# dwm1000v3.net
KiCad netlist of a schematic drawn in EAGLE
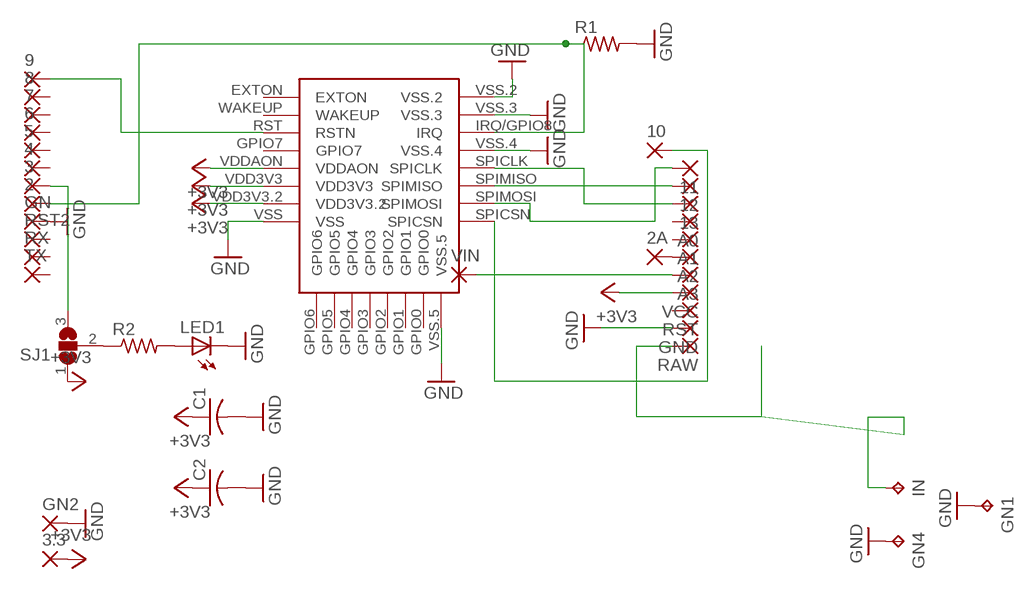
[diagram p0: schematic, sheet 1]

(export (version "E")
  (design (tool "Eeschema 10.0.6"))
  (components
    (comp (ref "2")
      (value "SMD2")
      (footprint "eagle-import:SMD1,27-2,54")
      (libsource (lib "eagle-import") (part "SMD2"))
    )
    (comp (ref "2A")
      (value "SMD2")
      (footprint "eagle-import:SMD1,27-2,54")
      (libsource (lib "eagle-import") (part "SMD2"))
    )
    (comp (ref "3")
      (value "SMD2")
      (footprint "eagle-import:SMD1,27-2,54")
      (libsource (lib "eagle-import") (part "SMD2"))
    )
    (comp (ref "3.3")
      (value "SMD2")
      (footprint "eagle-import:SMD1,27-2,54")
      (libsource (lib "eagle-import") (part "SMD2"))
    )
    (comp (ref "4")
      (value "SMD2")
      (footprint "eagle-import:SMD1,27-2,54")
      (libsource (lib "eagle-import") (part "SMD2"))
    )
    (comp (ref "5")
      (value "SMD2")
      (footprint "eagle-import:SMD1,27-2,54")
      (libsource (lib "eagle-import") (part "SMD2"))
    )
    (comp (ref "6")
      (value "SMD2")
      (footprint "eagle-import:SMD1,27-2,54")
      (libsource (lib "eagle-import") (part "SMD2"))
    )
    (comp (ref "7")
      (value "SMD2")
      (footprint "eagle-import:SMD1,27-2,54")
      (libsource (lib "eagle-import") (part "SMD2"))
    )
    (comp (ref "8")
      (value "SMD2")
      (footprint "eagle-import:SMD1,27-2,54")
      (libsource (lib "eagle-import") (part "SMD2"))
    )
    (comp (ref "9")
      (value "SMD2")
      (footprint "eagle-import:SMD1,27-2,54")
      (libsource (lib "eagle-import") (part "SMD2"))
    )
    (comp (ref "10")
      (value "SMD2")
      (footprint "eagle-import:SMD1,27-2,54")
      (libsource (lib "eagle-import") (part "SMD2"))
    )
    (comp (ref "11")
      (value "SMD2")
      (footprint "eagle-import:SMD1,27-2,54")
      (libsource (lib "eagle-import") (part "SMD2"))
    )
    (comp (ref "12")
      (value "SMD2")
      (footprint "eagle-import:SMD1,27-2,54")
      (libsource (lib "eagle-import") (part "SMD2"))
    )
    (comp (ref "13")
      (value "SMD2")
      (footprint "eagle-import:SMD1,27-2,54")
      (libsource (lib "eagle-import") (part "SMD2"))
    )
    (comp (ref "A0")
      (value "SMD2")
      (footprint "eagle-import:SMD1,27-2,54")
      (libsource (lib "eagle-import") (part "SMD2"))
    )
    (comp (ref "A1")
      (value "SMD2")
      (footprint "eagle-import:SMD1,27-2,54")
      (libsource (lib "eagle-import") (part "SMD2"))
    )
    (comp (ref "A2")
      (value "SMD2")
      (footprint "eagle-import:SMD1,27-2,54")
      (libsource (lib "eagle-import") (part "SMD2"))
    )
    (comp (ref "A3")
      (value "SMD2")
      (footprint "eagle-import:SMD1,27-2,54")
      (libsource (lib "eagle-import") (part "SMD2"))
    )
    (comp (ref "C1")
      (value "C-USC0805")
      (footprint "eagle-import:C0805")
      (libsource (lib "eagle-import") (part "C-USC0805"))
    )
    (comp (ref "C2")
      (value "C-USC0805")
      (footprint "eagle-import:C0805")
      (libsource (lib "eagle-import") (part "C-USC0805"))
    )
    (comp (ref "GN")
      (value "SMD2")
      (footprint "eagle-import:SMD1,27-2,54")
      (libsource (lib "eagle-import") (part "SMD2"))
    )
    (comp (ref "GN1")
      (value "TPTP13SQ")
      (footprint "eagle-import:TP13SQ")
      (libsource (lib "eagle-import") (part "TPTP13SQ"))
    )
    (comp (ref "GN2")
      (value "SMD2")
      (footprint "eagle-import:SMD1,27-2,54")
      (libsource (lib "eagle-import") (part "SMD2"))
    )
    (comp (ref "GN4")
      (value "TPTP13SQ")
      (footprint "eagle-import:TP13SQ")
      (libsource (lib "eagle-import") (part "TPTP13SQ"))
    )
    (comp (ref "GND")
      (value "SMD2")
      (footprint "eagle-import:SMD1,27-2,54")
      (libsource (lib "eagle-import") (part "SMD2"))
    )
    (comp (ref "IN")
      (value "TPTP13SQ")
      (footprint "eagle-import:TP13SQ")
      (libsource (lib "eagle-import") (part "TPTP13SQ"))
    )
    (comp (ref "LED1")
      (value "LEDCHIPLED_0805")
      (footprint "eagle-import:CHIPLED_0805")
      (libsource (lib "eagle-import") (part "LEDCHIPLED_0805"))
    )
    (comp (ref "R1")
      (value "R-US_R0603")
      (footprint "eagle-import:R0603")
      (libsource (lib "eagle-import") (part "R-US_R0603"))
    )
    (comp (ref "R2")
      (value "R-US_M0805")
      (footprint "eagle-import:M0805")
      (libsource (lib "eagle-import") (part "R-US_M0805"))
    )
    (comp (ref "RAW")
      (value "SMD2")
      (footprint "eagle-import:SMD1,27-2,54")
      (libsource (lib "eagle-import") (part "SMD2"))
    )
    (comp (ref "RST")
      (value "SMD2")
      (footprint "eagle-import:SMD1,27-2,54")
      (libsource (lib "eagle-import") (part "SMD2"))
    )
    (comp (ref "RST2")
      (value "SMD2")
      (footprint "eagle-import:SMD1,27-2,54")
      (libsource (lib "eagle-import") (part "SMD2"))
    )
    (comp (ref "RX")
      (value "SMD2")
      (footprint "eagle-import:SMD1,27-2,54")
      (libsource (lib "eagle-import") (part "SMD2"))
    )
    (comp (ref "SJ1")
      (value "SJ2W")
      (footprint "eagle-import:SJ_2")
      (libsource (lib "eagle-import") (part "SJ2W"))
    )
    (comp (ref "TX")
      (value "SMD2")
      (footprint "eagle-import:SMD1,27-2,54")
      (libsource (lib "eagle-import") (part "SMD2"))
    )
    (comp (ref "U$1")
      (value "DWM1000")
      (footprint "eagle-import:DWM1000")
      (libsource (lib "eagle-import") (part "DWM1000"))
    )
    (comp (ref "VCC")
      (value "SMD2")
      (footprint "eagle-import:SMD1,27-2,54")
      (libsource (lib "eagle-import") (part "SMD2"))
    )
    (comp (ref "VIN")
      (value "SMD2")
      (footprint "eagle-import:SMD1,27-2,54")
      (libsource (lib "eagle-import") (part "SMD2"))
    )
  )
  (nets
    (net (code "1") (name "+3V3") (class "Default")
      (node (ref "3.3") (pin "1") (pinfunction "P_1") (pintype "passive"))
      (node (ref "C1") (pin "1") (pinfunction "1_1") (pintype "passive"))
      (node (ref "C2") (pin "1") (pinfunction "1_1") (pintype "passive"))
      (node (ref "SJ1") (pin "1") (pinfunction "1_1") (pintype "passive"))
      (node (ref "U$1") (pin "VDD3V3") (pinfunction "VDD3V3_VDD3V3") (pintype "bidirectional"))
      (node (ref "U$1") (pin "VDD3V3.2") (pinfunction "VDD3V3.2_VDD3V3.2") (pintype "bidirectional"))
      (node (ref "U$1") (pin "VDDAON") (pinfunction "VDDAON_VDDAON") (pintype "bidirectional"))
      (node (ref "VCC") (pin "1") (pinfunction "P_1") (pintype "passive"))
    )
    (net (code "2") (name "GND") (class "Default")
      (node (ref "C1") (pin "2") (pinfunction "2_2") (pintype "passive"))
      (node (ref "C2") (pin "2") (pinfunction "2_2") (pintype "passive"))
      (node (ref "GN") (pin "1") (pinfunction "P_1") (pintype "passive"))
      (node (ref "GN1") (pin "TP") (pinfunction "TP_TP") (pintype "input"))
      (node (ref "GN2") (pin "1") (pinfunction "P_1") (pintype "passive"))
      (node (ref "GN4") (pin "TP") (pinfunction "TP_TP") (pintype "input"))
      (node (ref "GND") (pin "1") (pinfunction "P_1") (pintype "passive"))
      (node (ref "LED1") (pin "C") (pinfunction "C_C") (pintype "passive"))
      (node (ref "R1") (pin "2") (pinfunction "2_2") (pintype "passive"))
      (node (ref "U$1") (pin "VSS") (pinfunction "VSS_VSS") (pintype "bidirectional"))
      (node (ref "U$1") (pin "VSS.2") (pinfunction "VSS.2_VSS.2") (pintype "bidirectional"))
      (node (ref "U$1") (pin "VSS.3") (pinfunction "VSS.3_VSS.3") (pintype "bidirectional"))
      (node (ref "U$1") (pin "VSS.4") (pinfunction "VSS.4_VSS.4") (pintype "bidirectional"))
      (node (ref "U$1") (pin "VSS.5") (pinfunction "VSS.5_VSS.5") (pintype "bidirectional"))
    )
    (net (code "3") (name "Net-(2-P)") (class "Default")
      (node (ref "2") (pin "1") (pinfunction "P_1") (pintype "passive"))
      (node (ref "R1") (pin "1") (pinfunction "1_1") (pintype "passive"))
      (node (ref "U$1") (pin "IRQ/GPIO8") (pinfunction "IRQ_IRQ/GPIO8") (pintype "bidirectional"))
    )
    (net (code "4") (name "Net-(2A-P)") (class "Default")
      (node (ref "2A") (pin "1") (pinfunction "P_1") (pintype "passive"))
      (node (ref "A2") (pin "1") (pinfunction "P_1") (pintype "passive"))
    )
    (net (code "5") (name "Net-(3-P)") (class "Default")
      (node (ref "3") (pin "1") (pinfunction "P_1") (pintype "passive"))
      (node (ref "SJ1") (pin "3") (pinfunction "3_3") (pintype "passive"))
    )
    (net (code "6") (name "Net-(9-P)") (class "Default")
      (node (ref "9") (pin "1") (pinfunction "P_1") (pintype "passive"))
      (node (ref "U$1") (pin "RST") (pinfunction "RSTN_RST") (pintype "bidirectional"))
    )
    (net (code "7") (name "Net-(10-P)") (class "Default")
      (node (ref "10") (pin "1") (pinfunction "P_1") (pintype "passive"))
      (node (ref "U$1") (pin "SPICSN") (pinfunction "SPICSN_SPICSN") (pintype "bidirectional"))
    )
    (net (code "8") (name "Net-(11-P)") (class "Default")
      (node (ref "11") (pin "1") (pinfunction "P_1") (pintype "passive"))
      (node (ref "U$1") (pin "SPIMOSI") (pinfunction "SPIMOSI_SPIMOSI") (pintype "bidirectional"))
    )
    (net (code "9") (name "Net-(12-P)") (class "Default")
      (node (ref "12") (pin "1") (pinfunction "P_1") (pintype "passive"))
      (node (ref "U$1") (pin "SPIMISO") (pinfunction "SPIMISO_SPIMISO") (pintype "bidirectional"))
    )
    (net (code "10") (name "Net-(13-P)") (class "Default")
      (node (ref "13") (pin "1") (pinfunction "P_1") (pintype "passive"))
      (node (ref "U$1") (pin "SPICLK") (pinfunction "SPICLK_SPICLK") (pintype "bidirectional"))
    )
    (net (code "11") (name "Net-(A3-P)") (class "Default")
      (node (ref "A3") (pin "1") (pinfunction "P_1") (pintype "passive"))
      (node (ref "VIN") (pin "1") (pinfunction "P_1") (pintype "passive"))
    )
    (net (code "12") (name "Net-(LED1-PadA)") (class "Default")
      (node (ref "LED1") (pin "A") (pinfunction "A_A") (pintype "passive"))
      (node (ref "R2") (pin "2") (pinfunction "2_2") (pintype "passive"))
    )
    (net (code "13") (name "Net-(R2-Pad1)") (class "Default")
      (node (ref "R2") (pin "1") (pinfunction "1_1") (pintype "passive"))
      (node (ref "SJ1") (pin "2") (pinfunction "2_2") (pintype "passive"))
    )
    (net (code "14") (name "Net-(RAW-P)") (class "Default")
      (node (ref "IN") (pin "TP") (pinfunction "TP_TP") (pintype "input"))
      (node (ref "RAW") (pin "1") (pinfunction "P_1") (pintype "passive"))
    )
    (net (code "15") (name "unconnected-(4-P-Pad1)") (class "Default")
      (node (ref "4") (pin "1") (pinfunction "P_1") (pintype "passive"))
    )
    (net (code "16") (name "unconnected-(5-P-Pad1)") (class "Default")
      (node (ref "5") (pin "1") (pinfunction "P_1") (pintype "passive"))
    )
    (net (code "17") (name "unconnected-(6-P-Pad1)") (class "Default")
      (node (ref "6") (pin "1") (pinfunction "P_1") (pintype "passive"))
    )
    (net (code "18") (name "unconnected-(7-P-Pad1)") (class "Default")
      (node (ref "7") (pin "1") (pinfunction "P_1") (pintype "passive"))
    )
    (net (code "19") (name "unconnected-(8-P-Pad1)") (class "Default")
      (node (ref "8") (pin "1") (pinfunction "P_1") (pintype "passive"))
    )
    (net (code "20") (name "unconnected-(A0-P-Pad1)") (class "Default")
      (node (ref "A0") (pin "1") (pinfunction "P_1") (pintype "passive"))
    )
    (net (code "21") (name "unconnected-(A1-P-Pad1)") (class "Default")
      (node (ref "A1") (pin "1") (pinfunction "P_1") (pintype "passive"))
    )
    (net (code "22") (name "unconnected-(RST-P-Pad1)") (class "Default")
      (node (ref "RST") (pin "1") (pinfunction "P_1") (pintype "passive"))
    )
    (net (code "23") (name "unconnected-(RST2-P-Pad1)") (class "Default")
      (node (ref "RST2") (pin "1") (pinfunction "P_1") (pintype "passive"))
    )
    (net (code "24") (name "unconnected-(RX-P-Pad1)") (class "Default")
      (node (ref "RX") (pin "1") (pinfunction "P_1") (pintype "passive"))
    )
    (net (code "25") (name "unconnected-(TX-P-Pad1)") (class "Default")
      (node (ref "TX") (pin "1") (pinfunction "P_1") (pintype "passive"))
    )
    (net (code "26") (name "unconnected-(U$1-PadEXTON)") (class "Default")
      (node (ref "U$1") (pin "EXTON") (pinfunction "EXTON_EXTON") (pintype "bidirectional"))
    )
    (net (code "27") (name "unconnected-(U$1-PadGPIO0)") (class "Default")
      (node (ref "U$1") (pin "GPIO0") (pinfunction "GPIO0_GPIO0") (pintype "bidirectional"))
    )
    (net (code "28") (name "unconnected-(U$1-PadGPIO1)") (class "Default")
      (node (ref "U$1") (pin "GPIO1") (pinfunction "GPIO1_GPIO1") (pintype "bidirectional"))
    )
    (net (code "29") (name "unconnected-(U$1-PadGPIO2)") (class "Default")
      (node (ref "U$1") (pin "GPIO2") (pinfunction "GPIO2_GPIO2") (pintype "bidirectional"))
    )
    (net (code "30") (name "unconnected-(U$1-PadGPIO3)") (class "Default")
      (node (ref "U$1") (pin "GPIO3") (pinfunction "GPIO3_GPIO3") (pintype "bidirectional"))
    )
    (net (code "31") (name "unconnected-(U$1-PadGPIO4)") (class "Default")
      (node (ref "U$1") (pin "GPIO4") (pinfunction "GPIO4_GPIO4") (pintype "bidirectional"))
    )
    (net (code "32") (name "unconnected-(U$1-PadGPIO5)") (class "Default")
      (node (ref "U$1") (pin "GPIO5") (pinfunction "GPIO5_GPIO5") (pintype "bidirectional"))
    )
    (net (code "33") (name "unconnected-(U$1-PadGPIO6)") (class "Default")
      (node (ref "U$1") (pin "GPIO6") (pinfunction "GPIO6_GPIO6") (pintype "bidirectional"))
    )
    (net (code "34") (name "unconnected-(U$1-PadGPIO7)") (class "Default")
      (node (ref "U$1") (pin "GPIO7") (pinfunction "GPIO7_GPIO7") (pintype "bidirectional"))
    )
    (net (code "35") (name "unconnected-(U$1-PadWAKEUP)") (class "Default")
      (node (ref "U$1") (pin "WAKEUP") (pinfunction "WAKEUP_WAKEUP") (pintype "bidirectional"))
    )
  )
)
